# Carrier_MCU.net
KiCad netlist of a schematic drawn in Altium Designer
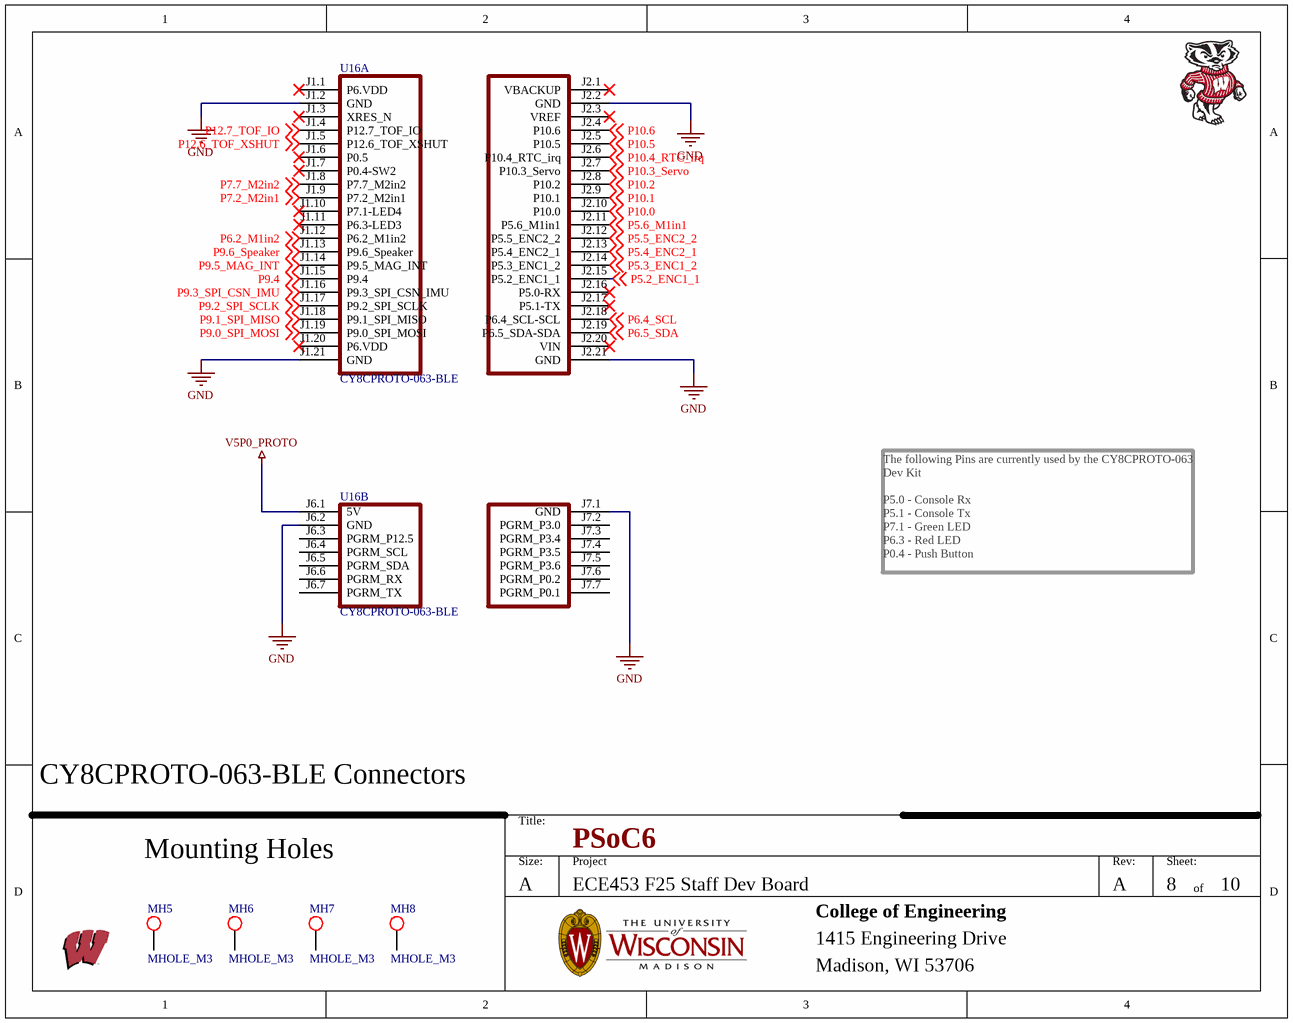
[diagram p0: Carrier_MCU.SchDoc]

(export (version "E")
  (design (tool "Eeschema 10.0.6"))
  (components
    (comp (ref "MH5")
      (value "MHOLE_M3")
      (footprint "MHOLE_M3")
      (description "Mounting Hole - M3 Metric")
      (libsource (lib "uw-madison-parts") (part "MHOLE_M3"))
    )
    (comp (ref "MH6")
      (value "MHOLE_M3")
      (footprint "MHOLE_M3")
      (description "Mounting Hole - M3 Metric")
      (libsource (lib "uw-madison-parts") (part "MHOLE_M3"))
    )
    (comp (ref "MH7")
      (value "MHOLE_M3")
      (footprint "MHOLE_M3")
      (description "Mounting Hole - M3 Metric")
      (libsource (lib "uw-madison-parts") (part "MHOLE_M3"))
    )
    (comp (ref "MH8")
      (value "MHOLE_M3")
      (footprint "MHOLE_M3")
      (description "Mounting Hole - M3 Metric")
      (libsource (lib "uw-madison-parts") (part "MHOLE_M3"))
    )
    (comp (ref "U16")
      (value "CY8CPROTO-063-BLE")
      (footprint "CY8CPROTO-063-BLE")
      (libsource (lib "ECE453_S24") (part "IC_CY8CPROTO-063-BLE"))
    )
  )
  (nets
    (net (code "1") (name "GND") (class "Default")
      (node (ref "U16") (pin "J1.2") (pinfunction "GND_J1.2") (pintype "passive"))
      (node (ref "U16") (pin "J1.21") (pinfunction "GND_J1.21") (pintype "passive"))
      (node (ref "U16") (pin "J2.2") (pinfunction "GND_J2.2") (pintype "passive"))
      (node (ref "U16") (pin "J2.21") (pinfunction "GND_J2.21") (pintype "passive"))
      (node (ref "U16") (pin "J6.2") (pinfunction "GND_J6.2") (pintype "passive"))
      (node (ref "U16") (pin "J7.1") (pinfunction "GND_J7.1") (pintype "passive"))
    )
    (net (code "2") (name "P5.2_ENC1_1") (class "Default")
      (node (ref "U16") (pin "J2.15") (pinfunction "P5.2_J2.15") (pintype "passive"))
    )
    (net (code "3") (name "P5.3_ENC1_2") (class "Default")
      (node (ref "U16") (pin "J2.14") (pinfunction "P5.3_J2.14") (pintype "passive"))
    )
    (net (code "4") (name "P5.4_ENC2_1") (class "Default")
      (node (ref "U16") (pin "J2.13") (pinfunction "P5.4_J2.13") (pintype "passive"))
    )
    (net (code "5") (name "P5.5_ENC2_2") (class "Default")
      (node (ref "U16") (pin "J2.12") (pinfunction "P5.5_J2.12") (pintype "passive"))
    )
    (net (code "6") (name "P5.6_M1in1") (class "Default")
      (node (ref "U16") (pin "J2.11") (pinfunction "P5.6_J2.11") (pintype "passive"))
    )
    (net (code "7") (name "P6.2_M1in2") (class "Default")
      (node (ref "U16") (pin "J1.12") (pinfunction "P6.2_J1.12") (pintype "passive"))
    )
    (net (code "8") (name "P6.4_SCL") (class "Default")
      (node (ref "U16") (pin "J2.18") (pinfunction "P6.4-SCL_J2.18") (pintype "passive"))
    )
    (net (code "9") (name "P6.5_SDA") (class "Default")
      (node (ref "U16") (pin "J2.19") (pinfunction "P6.5-SDA_J2.19") (pintype "passive"))
    )
    (net (code "10") (name "P7.2_M2in1") (class "Default")
      (node (ref "U16") (pin "J1.9") (pinfunction "P7.2_J1.9") (pintype "passive"))
    )
    (net (code "11") (name "P7.7_M2in2") (class "Default")
      (node (ref "U16") (pin "J1.8") (pinfunction "P7.7_J1.8") (pintype "passive"))
    )
    (net (code "12") (name "P9.0_SPI_MOSI") (class "Default")
      (node (ref "U16") (pin "J1.19") (pinfunction "P9.0_J1.19") (pintype "passive"))
    )
    (net (code "13") (name "P9.1_SPI_MISO") (class "Default")
      (node (ref "U16") (pin "J1.18") (pinfunction "P9.1_J1.18") (pintype "passive"))
    )
    (net (code "14") (name "P9.2_SPI_SCLK") (class "Default")
      (node (ref "U16") (pin "J1.17") (pinfunction "P9.2_J1.17") (pintype "passive"))
    )
    (net (code "15") (name "P9.3_SPI_CSN_IMU") (class "Default")
      (node (ref "U16") (pin "J1.16") (pinfunction "P9.3_J1.16") (pintype "passive"))
    )
    (net (code "16") (name "P9.4") (class "Default")
      (node (ref "U16") (pin "J1.15") (pinfunction "P9.4_J1.15") (pintype "passive"))
    )
    (net (code "17") (name "P9.5_MAG_INT") (class "Default")
      (node (ref "U16") (pin "J1.14") (pinfunction "P9.5_J1.14") (pintype "passive"))
    )
    (net (code "18") (name "P9.6_Speaker") (class "Default")
      (node (ref "U16") (pin "J1.13") (pinfunction "P9.6_J1.13") (pintype "passive"))
    )
    (net (code "19") (name "P10.0") (class "Default")
      (node (ref "U16") (pin "J2.10") (pinfunction "P10.0_J2.10") (pintype "passive"))
    )
    (net (code "20") (name "P10.1") (class "Default")
      (node (ref "U16") (pin "J2.9") (pinfunction "P10.1_J2.9") (pintype "passive"))
    )
    (net (code "21") (name "P10.2") (class "Default")
      (node (ref "U16") (pin "J2.8") (pinfunction "P10.2_J2.8") (pintype "passive"))
    )
    (net (code "22") (name "P10.3_Servo") (class "Default")
      (node (ref "U16") (pin "J2.7") (pinfunction "P10.3_J2.7") (pintype "passive"))
    )
    (net (code "23") (name "P10.4_RTC_irq") (class "Default")
      (node (ref "U16") (pin "J2.6") (pinfunction "P10.4_J2.6") (pintype "passive"))
    )
    (net (code "24") (name "P10.5") (class "Default")
      (node (ref "U16") (pin "J2.5") (pinfunction "P10.5_J2.5") (pintype "passive"))
    )
    (net (code "25") (name "P10.6") (class "Default")
      (node (ref "U16") (pin "J2.4") (pinfunction "P10.6_J2.4") (pintype "passive"))
    )
    (net (code "26") (name "P12.6_TOF_XSHUT") (class "Default")
      (node (ref "U16") (pin "J1.5") (pinfunction "P12.6_J1.5") (pintype "passive"))
    )
    (net (code "27") (name "P12.7_TOF_IO") (class "Default")
      (node (ref "U16") (pin "J1.4") (pinfunction "P12.7_J1.4") (pintype "passive"))
    )
    (net (code "28") (name "V5P0_PROTO") (class "Default")
      (node (ref "U16") (pin "J6.1") (pinfunction "5V_J6.1") (pintype "passive"))
    )
    (net (code "29") (name "unconnected-(MH5-Pad1)") (class "Default")
      (node (ref "MH5") (pin "1") (pintype "passive"))
    )
    (net (code "30") (name "unconnected-(MH6-Pad1)") (class "Default")
      (node (ref "MH6") (pin "1") (pintype "passive"))
    )
    (net (code "31") (name "unconnected-(MH7-Pad1)") (class "Default")
      (node (ref "MH7") (pin "1") (pintype "passive"))
    )
    (net (code "32") (name "unconnected-(MH8-Pad1)") (class "Default")
      (node (ref "MH8") (pin "1") (pintype "passive"))
    )
    (net (code "33") (name "unconnected-(U16A-P0.4-SW2-PadJ1.7)") (class "Default")
      (node (ref "U16") (pin "J1.7") (pinfunction "P0.4-SW2_J1.7") (pintype "passive+no_connect"))
    )
    (net (code "34") (name "unconnected-(U16A-P0.5-PadJ1.6)") (class "Default")
      (node (ref "U16") (pin "J1.6") (pinfunction "P0.5_J1.6") (pintype "passive+no_connect"))
    )
    (net (code "35") (name "unconnected-(U16A-P5.0-RX-PadJ2.16)") (class "Default")
      (node (ref "U16") (pin "J2.16") (pinfunction "P5.0-RX_J2.16") (pintype "passive+no_connect"))
    )
    (net (code "36") (name "unconnected-(U16A-P5.1-TX-PadJ2.17)") (class "Default")
      (node (ref "U16") (pin "J2.17") (pinfunction "P5.1-TX_J2.17") (pintype "passive+no_connect"))
    )
    (net (code "37") (name "unconnected-(U16A-P6.3-LED3-PadJ1.11)") (class "Default")
      (node (ref "U16") (pin "J1.11") (pinfunction "P6.3-LED3_J1.11") (pintype "passive+no_connect"))
    )
    (net (code "38") (name "unconnected-(U16A-P6.VDD-PadJ1.1)") (class "Default")
      (node (ref "U16") (pin "J1.1") (pinfunction "P6.VDD_J1.1") (pintype "passive+no_connect"))
    )
    (net (code "39") (name "unconnected-(U16A-P6.VDD-PadJ1.20)") (class "Default")
      (node (ref "U16") (pin "J1.20") (pinfunction "P6.VDD_J1.20") (pintype "passive+no_connect"))
    )
    (net (code "40") (name "unconnected-(U16A-P7.1-LED4-PadJ1.10)") (class "Default")
      (node (ref "U16") (pin "J1.10") (pinfunction "P7.1-LED4_J1.10") (pintype "passive+no_connect"))
    )
    (net (code "41") (name "unconnected-(U16A-VBACKUP-PadJ2.1)") (class "Default")
      (node (ref "U16") (pin "J2.1") (pinfunction "VBACKUP_J2.1") (pintype "passive+no_connect"))
    )
    (net (code "42") (name "unconnected-(U16A-VIN-PadJ2.20)") (class "Default")
      (node (ref "U16") (pin "J2.20") (pinfunction "VIN_J2.20") (pintype "passive+no_connect"))
    )
    (net (code "43") (name "unconnected-(U16A-VREF-PadJ2.3)") (class "Default")
      (node (ref "U16") (pin "J2.3") (pinfunction "VREF_J2.3") (pintype "passive+no_connect"))
    )
    (net (code "44") (name "unconnected-(U16A-XRES_N-PadJ1.3)") (class "Default")
      (node (ref "U16") (pin "J1.3") (pinfunction "XRES_N_J1.3") (pintype "passive+no_connect"))
    )
    (net (code "45") (name "unconnected-(U16B-PGRM_P0.1-PadJ7.7)") (class "Default")
      (node (ref "U16") (pin "J7.7") (pinfunction "PGRM_P0.1_J7.7") (pintype "passive"))
    )
    (net (code "46") (name "unconnected-(U16B-PGRM_P0.2-PadJ7.6)") (class "Default")
      (node (ref "U16") (pin "J7.6") (pinfunction "PGRM_P0.2_J7.6") (pintype "passive"))
    )
    (net (code "47") (name "unconnected-(U16B-PGRM_P3.0-PadJ7.2)") (class "Default")
      (node (ref "U16") (pin "J7.2") (pinfunction "PGRM_P3.0_J7.2") (pintype "passive"))
    )
    (net (code "48") (name "unconnected-(U16B-PGRM_P3.4-PadJ7.3)") (class "Default")
      (node (ref "U16") (pin "J7.3") (pinfunction "PGRM_P3.4_J7.3") (pintype "passive"))
    )
    (net (code "49") (name "unconnected-(U16B-PGRM_P3.5-PadJ7.4)") (class "Default")
      (node (ref "U16") (pin "J7.4") (pinfunction "PGRM_P3.5_J7.4") (pintype "passive"))
    )
    (net (code "50") (name "unconnected-(U16B-PGRM_P3.6-PadJ7.5)") (class "Default")
      (node (ref "U16") (pin "J7.5") (pinfunction "PGRM_P3.6_J7.5") (pintype "passive"))
    )
    (net (code "51") (name "unconnected-(U16B-PGRM_P12.5-PadJ6.3)") (class "Default")
      (node (ref "U16") (pin "J6.3") (pinfunction "PGRM_P12.5_J6.3") (pintype "passive"))
    )
    (net (code "52") (name "unconnected-(U16B-PGRM_RX-PadJ6.6)") (class "Default")
      (node (ref "U16") (pin "J6.6") (pinfunction "PGRM_RX_J6.6") (pintype "passive"))
    )
    (net (code "53") (name "unconnected-(U16B-PGRM_SCL-PadJ6.4)") (class "Default")
      (node (ref "U16") (pin "J6.4") (pinfunction "PGRM_SCL_J6.4") (pintype "passive"))
    )
    (net (code "54") (name "unconnected-(U16B-PGRM_SDA-PadJ6.5)") (class "Default")
      (node (ref "U16") (pin "J6.5") (pinfunction "PGRM_SDA_J6.5") (pintype "passive"))
    )
    (net (code "55") (name "unconnected-(U16B-PGRM_TX-PadJ6.7)") (class "Default")
      (node (ref "U16") (pin "J6.7") (pinfunction "PGRM_TX_J6.7") (pintype "passive"))
    )
  )
)
